# 2uprava5.net
KiCad netlist of a schematic drawn in EAGLE
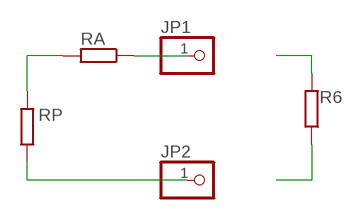
[diagram p0: schematic, sheet 1]

(export (version "E")
  (design (tool "Eeschema 10.0.6"))
  (components
    (comp (ref "JP1")
      (value "PINHD-1X1")
      (footprint "eagle-import:1X01")
      (libsource (lib "eagle-import") (part "PINHD-1X1"))
    )
    (comp (ref "JP2")
      (value "PINHD-1X1")
      (footprint "eagle-import:1X01")
      (libsource (lib "eagle-import") (part "PINHD-1X1"))
    )
    (comp (ref "R6")
      (value "200R")
      (footprint "eagle-import:0204_7")
      (libsource (lib "eagle-import") (part "R-EU_0204/7"))
    )
    (comp (ref "RA")
      (value "570R")
      (footprint "eagle-import:0204_7")
      (libsource (lib "eagle-import") (part "R-EU_0204/7"))
    )
    (comp (ref "RP")
      (value "610R")
      (footprint "eagle-import:0204_7")
      (libsource (lib "eagle-import") (part "R-EU_0204/7"))
    )
  )
  (nets
    (net (code "1") (name "Net-(JP1-Pad1)") (class "Default")
      (node (ref "JP1") (pin "1") (pinfunction "1_1") (pintype "passive"))
      (node (ref "RA") (pin "1") (pinfunction "1_1") (pintype "passive"))
    )
    (net (code "2") (name "Net-(JP2-Pad1)") (class "Default")
      (node (ref "JP2") (pin "1") (pinfunction "1_1") (pintype "passive"))
      (node (ref "RP") (pin "1") (pinfunction "1_1") (pintype "passive"))
    )
    (net (code "3") (name "Net-(RA-Pad2)") (class "Default")
      (node (ref "RA") (pin "2") (pinfunction "2_2") (pintype "passive"))
      (node (ref "RP") (pin "2") (pinfunction "2_2") (pintype "passive"))
    )
    (net (code "4") (name "unconnected-(R6-Pad1)") (class "Default")
      (node (ref "R6") (pin "1") (pinfunction "1_1") (pintype "passive"))
    )
    (net (code "5") (name "unconnected-(R6-Pad2)") (class "Default")
      (node (ref "R6") (pin "2") (pinfunction "2_2") (pintype "passive"))
    )
  )
)
